# ESP8266_Module.net
KiCad netlist of a schematic drawn in Altium Designer
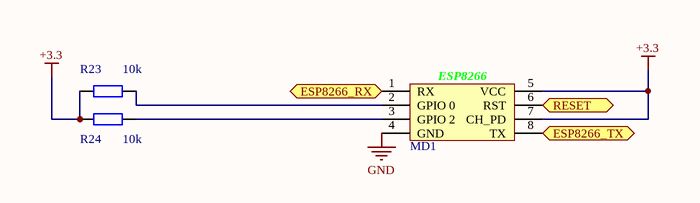
[diagram p0: ESP8266_Module.SchDoc]

(export (version "E")
  (design (tool "Eeschema 10.0.6"))
  (components
    (comp (ref "MD1")
      (value "ESP8266 Module")
      (footprint "ESP2866 Module")
      (libsource (lib "Altium_Lib_by_KhueNguyenCreator") (part "ESP8266 Module"))
    )
    (comp (ref "R23")
      (value "10k")
      (footprint "tro smd 0603")
      (description "Dán")
      (libsource (lib "Altium_Lib_by_KhueNguyenCreator") (part "Tro 0603 1% 10k"))
    )
    (comp (ref "R24")
      (value "10k")
      (footprint "tro smd 0603")
      (description "Dán")
      (libsource (lib "Altium_Lib_by_KhueNguyenCreator") (part "Tro 0603 1% 10k"))
    )
  )
  (nets
    (net (code "1") (name "+3.3") (class "Default")
      (node (ref "MD1") (pin "5") (pinfunction "VCC_5") (pintype "passive"))
      (node (ref "MD1") (pin "7") (pinfunction "CH_PD_7") (pintype "passive"))
      (node (ref "R23") (pin "1") (pinfunction "1_1") (pintype "passive"))
      (node (ref "R24") (pin "1") (pinfunction "1_1") (pintype "passive"))
    )
    (net (code "2") (name "/ESP8266_RX") (class "Default")
      (node (ref "MD1") (pin "1") (pinfunction "RX_1") (pintype "passive"))
    )
    (net (code "3") (name "/ESP8266_TX") (class "Default")
      (node (ref "MD1") (pin "8") (pinfunction "TX_8") (pintype "passive"))
    )
    (net (code "4") (name "/RESET") (class "Default")
      (node (ref "MD1") (pin "6") (pinfunction "RST_6") (pintype "passive"))
    )
    (net (code "5") (name "GND") (class "Default")
      (node (ref "MD1") (pin "4") (pinfunction "GND_4") (pintype "passive"))
    )
    (net (code "6") (name "Net-(MD1-GPIO_0)") (class "Default")
      (node (ref "MD1") (pin "2") (pinfunction "GPIO_0_2") (pintype "passive"))
      (node (ref "R23") (pin "2") (pinfunction "2_2") (pintype "passive"))
    )
    (net (code "7") (name "Net-(MD1-GPIO_2)") (class "Default")
      (node (ref "MD1") (pin "3") (pinfunction "GPIO_2_3") (pintype "passive"))
      (node (ref "R24") (pin "2") (pinfunction "2_2") (pintype "passive"))
    )
  )
)
